# v1.net
KiCad netlist of a schematic drawn in EAGLE
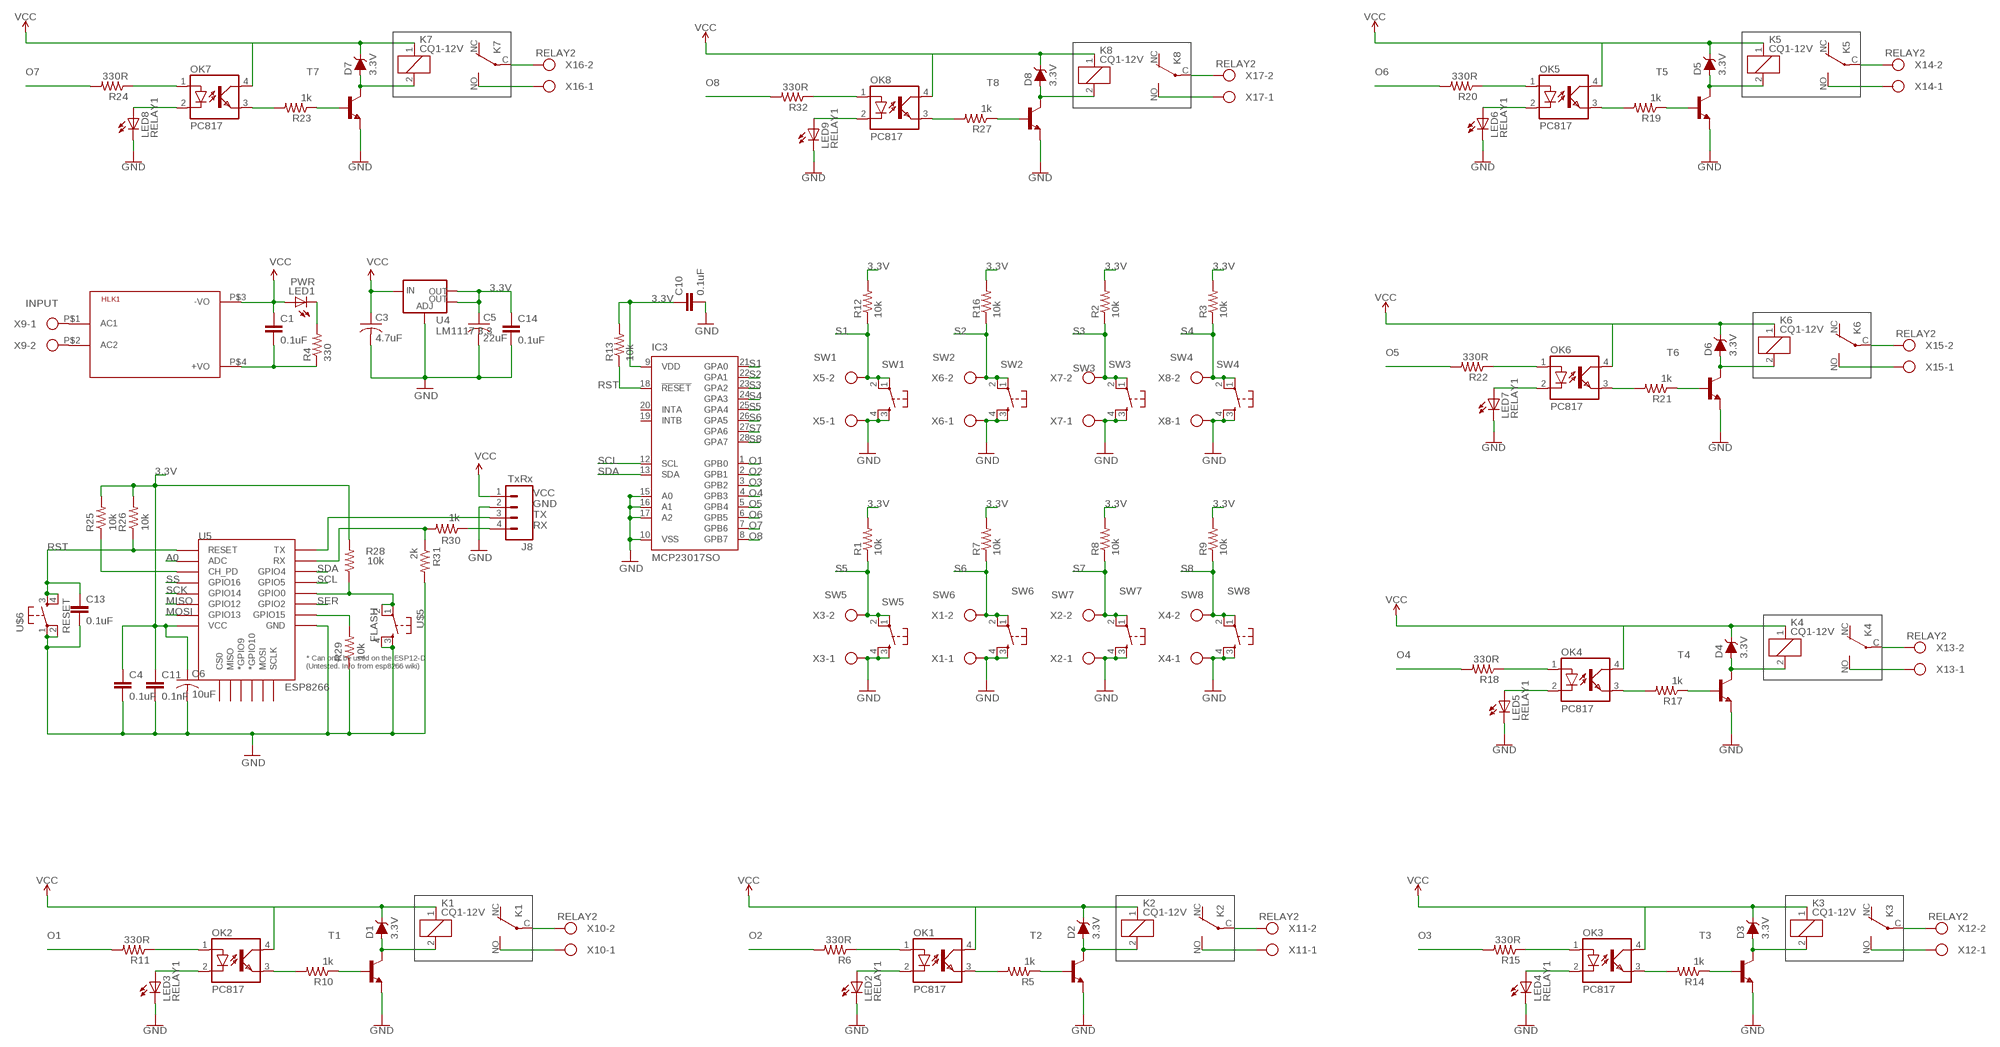
[diagram p0: schematic, sheet 1]

(export (version "E")
  (design (tool "Eeschema 10.0.6"))
  (components
    (comp (ref "C1")
      (value "0.1uF")
      (footprint "eagle-import:0805")
      (libsource (lib "eagle-import") (part "CAP0805"))
    )
    (comp (ref "C3")
      (value "4.7uF")
      (footprint "eagle-import:C1206")
      (libsource (lib "eagle-import") (part "C-USC1206"))
    )
    (comp (ref "C4")
      (value "0.1uF")
      (footprint "eagle-import:0805")
      (libsource (lib "eagle-import") (part "CAP0805"))
    )
    (comp (ref "C5")
      (value "22uF")
      (footprint "eagle-import:C1206")
      (libsource (lib "eagle-import") (part "C-USC1206"))
    )
    (comp (ref "C6")
      (value "10uF")
      (footprint "eagle-import:C1206")
      (libsource (lib "eagle-import") (part "C-USC1206"))
    )
    (comp (ref "C10")
      (value "0.1uF")
      (footprint "eagle-import:0805")
      (libsource (lib "eagle-import") (part "CAP0805"))
    )
    (comp (ref "C11")
      (value "0.1nF")
      (footprint "eagle-import:0805")
      (libsource (lib "eagle-import") (part "CAP0805"))
    )
    (comp (ref "C13")
      (value "0.1uF")
      (footprint "eagle-import:0805")
      (libsource (lib "eagle-import") (part "CAP0805"))
    )
    (comp (ref "C14")
      (value "0.1uF")
      (footprint "eagle-import:0805")
      (libsource (lib "eagle-import") (part "CAP0805"))
    )
    (comp (ref "D1")
      (value "3.3V")
      (footprint "eagle-import:SOD-323")
      (libsource (lib "eagle-import") (part "DIODE-ZENER-MM3Z3V3T1G"))
    )
    (comp (ref "D2")
      (value "3.3V")
      (footprint "eagle-import:SOD-323")
      (libsource (lib "eagle-import") (part "DIODE-ZENER-MM3Z3V3T1G"))
    )
    (comp (ref "D3")
      (value "3.3V")
      (footprint "eagle-import:SOD-323")
      (libsource (lib "eagle-import") (part "DIODE-ZENER-MM3Z3V3T1G"))
    )
    (comp (ref "D4")
      (value "3.3V")
      (footprint "eagle-import:SOD-323")
      (libsource (lib "eagle-import") (part "DIODE-ZENER-MM3Z3V3T1G"))
    )
    (comp (ref "D5")
      (value "3.3V")
      (footprint "eagle-import:SOD-323")
      (libsource (lib "eagle-import") (part "DIODE-ZENER-MM3Z3V3T1G"))
    )
    (comp (ref "D6")
      (value "3.3V")
      (footprint "eagle-import:SOD-323")
      (libsource (lib "eagle-import") (part "DIODE-ZENER-MM3Z3V3T1G"))
    )
    (comp (ref "D7")
      (value "3.3V")
      (footprint "eagle-import:SOD-323")
      (libsource (lib "eagle-import") (part "DIODE-ZENER-MM3Z3V3T1G"))
    )
    (comp (ref "D8")
      (value "3.3V")
      (footprint "eagle-import:SOD-323")
      (libsource (lib "eagle-import") (part "DIODE-ZENER-MM3Z3V3T1G"))
    )
    (comp (ref "HLK1")
      (value "HLK-PM013W")
      (footprint "eagle-import:HLK-PM01")
      (libsource (lib "eagle-import") (part "HLK-PM013W"))
    )
    (comp (ref "IC3")
      (value "MCP23017SO")
      (footprint "eagle-import:SO28W")
      (fields (field (name "MF") "MICROCHIP") (field (name "MPN") "MCP23017-E/SO"))
      (libsource (lib "eagle-import") (part "MCP23017SO"))
    )
    (comp (ref "J8")
      (value "TxRx")
      (footprint "eagle-import:MOLEX-1X4")
      (libsource (lib "eagle-import") (part "M04POLAR"))
    )
    (comp (ref "K1")
      (value "CQ1-12V")
      (footprint "eagle-import:CQ1")
      (libsource (lib "eagle-import") (part "CQ1-12V"))
    )
    (comp (ref "K2")
      (value "CQ1-12V")
      (footprint "eagle-import:CQ1")
      (libsource (lib "eagle-import") (part "CQ1-12V"))
    )
    (comp (ref "K3")
      (value "CQ1-12V")
      (footprint "eagle-import:CQ1")
      (libsource (lib "eagle-import") (part "CQ1-12V"))
    )
    (comp (ref "K4")
      (value "CQ1-12V")
      (footprint "eagle-import:CQ1")
      (libsource (lib "eagle-import") (part "CQ1-12V"))
    )
    (comp (ref "K5")
      (value "CQ1-12V")
      (footprint "eagle-import:CQ1")
      (libsource (lib "eagle-import") (part "CQ1-12V"))
    )
    (comp (ref "K6")
      (value "CQ1-12V")
      (footprint "eagle-import:CQ1")
      (libsource (lib "eagle-import") (part "CQ1-12V"))
    )
    (comp (ref "K7")
      (value "CQ1-12V")
      (footprint "eagle-import:CQ1")
      (libsource (lib "eagle-import") (part "CQ1-12V"))
    )
    (comp (ref "K8")
      (value "CQ1-12V")
      (footprint "eagle-import:CQ1")
      (libsource (lib "eagle-import") (part "CQ1-12V"))
    )
    (comp (ref "LED1")
      (value "PWR")
      (footprint "eagle-import:CHIP-LED0805")
      (libsource (lib "eagle-import") (part "LEDCHIP-LED0805"))
    )
    (comp (ref "LED2")
      (value "RELAY1")
      (footprint "eagle-import:CHIP-LED0805")
      (libsource (lib "eagle-import") (part "LEDCHIP-LED0805"))
    )
    (comp (ref "LED3")
      (value "RELAY1")
      (footprint "eagle-import:CHIP-LED0805")
      (libsource (lib "eagle-import") (part "LEDCHIP-LED0805"))
    )
    (comp (ref "LED4")
      (value "RELAY1")
      (footprint "eagle-import:CHIP-LED0805")
      (libsource (lib "eagle-import") (part "LEDCHIP-LED0805"))
    )
    (comp (ref "LED5")
      (value "RELAY1")
      (footprint "eagle-import:CHIP-LED0805")
      (libsource (lib "eagle-import") (part "LEDCHIP-LED0805"))
    )
    (comp (ref "LED6")
      (value "RELAY1")
      (footprint "eagle-import:CHIP-LED0805")
      (libsource (lib "eagle-import") (part "LEDCHIP-LED0805"))
    )
    (comp (ref "LED7")
      (value "RELAY1")
      (footprint "eagle-import:CHIP-LED0805")
      (libsource (lib "eagle-import") (part "LEDCHIP-LED0805"))
    )
    (comp (ref "LED8")
      (value "RELAY1")
      (footprint "eagle-import:CHIP-LED0805")
      (libsource (lib "eagle-import") (part "LEDCHIP-LED0805"))
    )
    (comp (ref "LED9")
      (value "RELAY1")
      (footprint "eagle-import:CHIP-LED0805")
      (libsource (lib "eagle-import") (part "LEDCHIP-LED0805"))
    )
    (comp (ref "OK1")
      (value "PC817")
      (footprint "eagle-import:DIL04")
      (fields (field (name "MPN") "PC817X4J000F"))
      (libsource (lib "eagle-import") (part "PC817"))
    )
    (comp (ref "OK2")
      (value "PC817")
      (footprint "eagle-import:DIL04")
      (fields (field (name "MPN") "PC817X4J000F"))
      (libsource (lib "eagle-import") (part "PC817"))
    )
    (comp (ref "OK3")
      (value "PC817")
      (footprint "eagle-import:DIL04")
      (fields (field (name "MPN") "PC817X4J000F"))
      (libsource (lib "eagle-import") (part "PC817"))
    )
    (comp (ref "OK4")
      (value "PC817")
      (footprint "eagle-import:DIL04")
      (fields (field (name "MPN") "PC817X4J000F"))
      (libsource (lib "eagle-import") (part "PC817"))
    )
    (comp (ref "OK5")
      (value "PC817")
      (footprint "eagle-import:DIL04")
      (fields (field (name "MPN") "PC817X4J000F"))
      (libsource (lib "eagle-import") (part "PC817"))
    )
    (comp (ref "OK6")
      (value "PC817")
      (footprint "eagle-import:DIL04")
      (fields (field (name "MPN") "PC817X4J000F"))
      (libsource (lib "eagle-import") (part "PC817"))
    )
    (comp (ref "OK7")
      (value "PC817")
      (footprint "eagle-import:DIL04")
      (fields (field (name "MPN") "PC817X4J000F"))
      (libsource (lib "eagle-import") (part "PC817"))
    )
    (comp (ref "OK8")
      (value "PC817")
      (footprint "eagle-import:DIL04")
      (fields (field (name "MPN") "PC817X4J000F"))
      (libsource (lib "eagle-import") (part "PC817"))
    )
    (comp (ref "R1")
      (value "10k")
      (footprint "eagle-import:0805")
      (libsource (lib "eagle-import") (part "RESISTOR0805-RES"))
    )
    (comp (ref "R2")
      (value "10k")
      (footprint "eagle-import:0805")
      (libsource (lib "eagle-import") (part "RESISTOR0805-RES"))
    )
    (comp (ref "R3")
      (value "10k")
      (footprint "eagle-import:0805")
      (libsource (lib "eagle-import") (part "RESISTOR0805-RES"))
    )
    (comp (ref "R4")
      (value "330")
      (footprint "eagle-import:0805")
      (libsource (lib "eagle-import") (part "RESISTOR0805-RES"))
    )
    (comp (ref "R5")
      (value "1k")
      (footprint "eagle-import:0805")
      (libsource (lib "eagle-import") (part "RESISTOR0805-RES"))
    )
    (comp (ref "R6")
      (value "330R")
      (footprint "eagle-import:0805")
      (libsource (lib "eagle-import") (part "RESISTOR0805-RES"))
    )
    (comp (ref "R7")
      (value "10k")
      (footprint "eagle-import:0805")
      (libsource (lib "eagle-import") (part "RESISTOR0805-RES"))
    )
    (comp (ref "R8")
      (value "10k")
      (footprint "eagle-import:0805")
      (libsource (lib "eagle-import") (part "RESISTOR0805-RES"))
    )
    (comp (ref "R9")
      (value "10k")
      (footprint "eagle-import:0805")
      (libsource (lib "eagle-import") (part "RESISTOR0805-RES"))
    )
    (comp (ref "R10")
      (value "1k")
      (footprint "eagle-import:0805")
      (libsource (lib "eagle-import") (part "RESISTOR0805-RES"))
    )
    (comp (ref "R11")
      (value "330R")
      (footprint "eagle-import:0805")
      (libsource (lib "eagle-import") (part "RESISTOR0805-RES"))
    )
    (comp (ref "R12")
      (value "10k")
      (footprint "eagle-import:0805")
      (libsource (lib "eagle-import") (part "RESISTOR0805-RES"))
    )
    (comp (ref "R13")
      (value "10k")
      (footprint "eagle-import:0805")
      (libsource (lib "eagle-import") (part "RESISTOR0805-RES"))
    )
    (comp (ref "R14")
      (value "1k")
      (footprint "eagle-import:0805")
      (libsource (lib "eagle-import") (part "RESISTOR0805-RES"))
    )
    (comp (ref "R15")
      (value "330R")
      (footprint "eagle-import:0805")
      (libsource (lib "eagle-import") (part "RESISTOR0805-RES"))
    )
    (comp (ref "R16")
      (value "10k")
      (footprint "eagle-import:0805")
      (libsource (lib "eagle-import") (part "RESISTOR0805-RES"))
    )
    (comp (ref "R17")
      (value "1k")
      (footprint "eagle-import:0805")
      (libsource (lib "eagle-import") (part "RESISTOR0805-RES"))
    )
    (comp (ref "R18")
      (value "330R")
      (footprint "eagle-import:0805")
      (libsource (lib "eagle-import") (part "RESISTOR0805-RES"))
    )
    (comp (ref "R19")
      (value "1k")
      (footprint "eagle-import:0805")
      (libsource (lib "eagle-import") (part "RESISTOR0805-RES"))
    )
    (comp (ref "R20")
      (value "330R")
      (footprint "eagle-import:0805")
      (libsource (lib "eagle-import") (part "RESISTOR0805-RES"))
    )
    (comp (ref "R21")
      (value "1k")
      (footprint "eagle-import:0805")
      (libsource (lib "eagle-import") (part "RESISTOR0805-RES"))
    )
    (comp (ref "R22")
      (value "330R")
      (footprint "eagle-import:0805")
      (libsource (lib "eagle-import") (part "RESISTOR0805-RES"))
    )
    (comp (ref "R23")
      (value "1k")
      (footprint "eagle-import:0805")
      (libsource (lib "eagle-import") (part "RESISTOR0805-RES"))
    )
    (comp (ref "R24")
      (value "330R")
      (footprint "eagle-import:0805")
      (libsource (lib "eagle-import") (part "RESISTOR0805-RES"))
    )
    (comp (ref "R25")
      (value "10k")
      (footprint "eagle-import:0805")
      (libsource (lib "eagle-import") (part "RESISTOR0805-RES"))
    )
    (comp (ref "R26")
      (value "10k")
      (footprint "eagle-import:0805")
      (libsource (lib "eagle-import") (part "RESISTOR0805-RES"))
    )
    (comp (ref "R27")
      (value "1k")
      (footprint "eagle-import:0805")
      (libsource (lib "eagle-import") (part "RESISTOR0805-RES"))
    )
    (comp (ref "R28")
      (value "10k")
      (footprint "eagle-import:0805")
      (libsource (lib "eagle-import") (part "RESISTOR0805-RES"))
    )
    (comp (ref "R29")
      (value "10k")
      (footprint "eagle-import:0805")
      (libsource (lib "eagle-import") (part "RESISTOR0805-RES"))
    )
    (comp (ref "R30")
      (value "1k")
      (footprint "eagle-import:0805")
      (libsource (lib "eagle-import") (part "RESISTOR0805-RES"))
    )
    (comp (ref "R31")
      (value "2k")
      (footprint "eagle-import:0805")
      (libsource (lib "eagle-import") (part "RESISTOR0805-RES"))
    )
    (comp (ref "R32")
      (value "330R")
      (footprint "eagle-import:0805")
      (libsource (lib "eagle-import") (part "RESISTOR0805-RES"))
    )
    (comp (ref "T1")
      (value "-NPN-SOT23-BEC")
      (footprint "eagle-import:SOT23-BEC")
      (libsource (lib "eagle-import") (part "-NPN-SOT23-BEC"))
    )
    (comp (ref "T2")
      (value "-NPN-SOT23-BEC")
      (footprint "eagle-import:SOT23-BEC")
      (libsource (lib "eagle-import") (part "-NPN-SOT23-BEC"))
    )
    (comp (ref "T3")
      (value "-NPN-SOT23-BEC")
      (footprint "eagle-import:SOT23-BEC")
      (libsource (lib "eagle-import") (part "-NPN-SOT23-BEC"))
    )
    (comp (ref "T4")
      (value "-NPN-SOT23-BEC")
      (footprint "eagle-import:SOT23-BEC")
      (libsource (lib "eagle-import") (part "-NPN-SOT23-BEC"))
    )
    (comp (ref "T5")
      (value "-NPN-SOT23-BEC")
      (footprint "eagle-import:SOT23-BEC")
      (libsource (lib "eagle-import") (part "-NPN-SOT23-BEC"))
    )
    (comp (ref "T6")
      (value "-NPN-SOT23-BEC")
      (footprint "eagle-import:SOT23-BEC")
      (libsource (lib "eagle-import") (part "-NPN-SOT23-BEC"))
    )
    (comp (ref "T7")
      (value "-NPN-SOT23-BEC")
      (footprint "eagle-import:SOT23-BEC")
      (libsource (lib "eagle-import") (part "-NPN-SOT23-BEC"))
    )
    (comp (ref "T8")
      (value "-NPN-SOT23-BEC")
      (footprint "eagle-import:SOT23-BEC")
      (libsource (lib "eagle-import") (part "-NPN-SOT23-BEC"))
    )
    (comp (ref "U$1")
      (value "SW1")
      (footprint "eagle-import:TAC-SWITCH-PTH")
      (libsource (lib "eagle-import") (part "TACTILE-SWITCH-PTH"))
    )
    (comp (ref "U$2")
      (value "SW2")
      (footprint "eagle-import:TAC-SWITCH-PTH")
      (libsource (lib "eagle-import") (part "TACTILE-SWITCH-PTH"))
    )
    (comp (ref "U$3")
      (value "SW5")
      (footprint "eagle-import:TAC-SWITCH-PTH")
      (libsource (lib "eagle-import") (part "TACTILE-SWITCH-PTH"))
    )
    (comp (ref "U$4")
      (value "SW3")
      (footprint "eagle-import:TAC-SWITCH-PTH")
      (libsource (lib "eagle-import") (part "TACTILE-SWITCH-PTH"))
    )
    (comp (ref "U$5")
      (value "FLASH")
      (footprint "eagle-import:TAC-SWITCH-PTH")
      (libsource (lib "eagle-import") (part "TACTILE-SWITCH-PTH"))
    )
    (comp (ref "U$6")
      (value "RESET")
      (footprint "eagle-import:TAC-SWITCH-PTH")
      (libsource (lib "eagle-import") (part "TACTILE-SWITCH-PTH"))
    )
    (comp (ref "U$7")
      (value "SW4")
      (footprint "eagle-import:TAC-SWITCH-PTH")
      (libsource (lib "eagle-import") (part "TACTILE-SWITCH-PTH"))
    )
    (comp (ref "U$8")
      (value "SW6")
      (footprint "eagle-import:TAC-SWITCH-PTH")
      (libsource (lib "eagle-import") (part "TACTILE-SWITCH-PTH"))
    )
    (comp (ref "U$9")
      (value "SW7")
      (footprint "eagle-import:TAC-SWITCH-PTH")
      (libsource (lib "eagle-import") (part "TACTILE-SWITCH-PTH"))
    )
    (comp (ref "U$10")
      (value "SW8")
      (footprint "eagle-import:TAC-SWITCH-PTH")
      (libsource (lib "eagle-import") (part "TACTILE-SWITCH-PTH"))
    )
    (comp (ref "U4")
      (value "LM1117 3.3")
      (footprint "eagle-import:SOT223")
      (libsource (lib "eagle-import") (part "V_REG_LM1117SOT223"))
    )
    (comp (ref "U5")
      (value "ESP8266")
      (footprint "eagle-import:ESP12E-SMD")
      (libsource (lib "eagle-import") (part "ESP12ESMD"))
    )
    (comp (ref "X1")
      (value "SW6")
      (footprint "eagle-import:W237-102")
      (fields (field (name "MPN") "237-102"))
      (libsource (lib "eagle-import") (part "W237-102"))
    )
    (comp (ref "X2")
      (value "SW7")
      (footprint "eagle-import:W237-102")
      (fields (field (name "MPN") "237-102"))
      (libsource (lib "eagle-import") (part "W237-102"))
    )
    (comp (ref "X3")
      (value "SW5")
      (footprint "eagle-import:W237-102")
      (fields (field (name "MPN") "237-102"))
      (libsource (lib "eagle-import") (part "W237-102"))
    )
    (comp (ref "X4")
      (value "SW8")
      (footprint "eagle-import:W237-102")
      (fields (field (name "MPN") "237-102"))
      (libsource (lib "eagle-import") (part "W237-102"))
    )
    (comp (ref "X5")
      (value "SW1")
      (footprint "eagle-import:W237-102")
      (fields (field (name "MPN") "237-102"))
      (libsource (lib "eagle-import") (part "W237-102"))
    )
    (comp (ref "X6")
      (value "SW2")
      (footprint "eagle-import:W237-102")
      (fields (field (name "MPN") "237-102"))
      (libsource (lib "eagle-import") (part "W237-102"))
    )
    (comp (ref "X7")
      (value "SW3")
      (footprint "eagle-import:W237-102")
      (fields (field (name "MPN") "237-102"))
      (libsource (lib "eagle-import") (part "W237-102"))
    )
    (comp (ref "X8")
      (value "SW4")
      (footprint "eagle-import:W237-102")
      (fields (field (name "MPN") "237-102"))
      (libsource (lib "eagle-import") (part "W237-102"))
    )
    (comp (ref "X9")
      (value "INPUT")
      (footprint "eagle-import:W237-102")
      (fields (field (name "MPN") "237-102"))
      (libsource (lib "eagle-import") (part "W237-102"))
    )
    (comp (ref "X10")
      (value "RELAY2")
      (footprint "eagle-import:W237-102")
      (fields (field (name "MPN") "237-102"))
      (libsource (lib "eagle-import") (part "W237-102"))
    )
    (comp (ref "X11")
      (value "RELAY2")
      (footprint "eagle-import:W237-102")
      (fields (field (name "MPN") "237-102"))
      (libsource (lib "eagle-import") (part "W237-102"))
    )
    (comp (ref "X12")
      (value "RELAY2")
      (footprint "eagle-import:W237-102")
      (fields (field (name "MPN") "237-102"))
      (libsource (lib "eagle-import") (part "W237-102"))
    )
    (comp (ref "X13")
      (value "RELAY2")
      (footprint "eagle-import:W237-102")
      (fields (field (name "MPN") "237-102"))
      (libsource (lib "eagle-import") (part "W237-102"))
    )
    (comp (ref "X14")
      (value "RELAY2")
      (footprint "eagle-import:W237-102")
      (fields (field (name "MPN") "237-102"))
      (libsource (lib "eagle-import") (part "W237-102"))
    )
    (comp (ref "X15")
      (value "RELAY2")
      (footprint "eagle-import:W237-102")
      (fields (field (name "MPN") "237-102"))
      (libsource (lib "eagle-import") (part "W237-102"))
    )
    (comp (ref "X16")
      (value "RELAY2")
      (footprint "eagle-import:W237-102")
      (fields (field (name "MPN") "237-102"))
      (libsource (lib "eagle-import") (part "W237-102"))
    )
    (comp (ref "X17")
      (value "RELAY2")
      (footprint "eagle-import:W237-102")
      (fields (field (name "MPN") "237-102"))
      (libsource (lib "eagle-import") (part "W237-102"))
    )
  )
  (nets
    (net (code "1") (name "/3.3V") (class "Default")
      (node (ref "C10") (pin "1") (pinfunction "1_1") (pintype "passive"))
      (node (ref "C11") (pin "1") (pinfunction "1_1") (pintype "passive"))
      (node (ref "C14") (pin "1") (pinfunction "1_1") (pintype "passive"))
      (node (ref "C4") (pin "1") (pinfunction "1_1") (pintype "passive"))
      (node (ref "C5") (pin "1") (pinfunction "1_1") (pintype "passive"))
      (node (ref "C6") (pin "1") (pinfunction "1_1") (pintype "passive"))
      (node (ref "IC3") (pin "9") (pinfunction "VDD_9") (pintype "power_in"))
      (node (ref "R1") (pin "2") (pinfunction "2_2") (pintype "passive"))
      (node (ref "R12") (pin "2") (pinfunction "2_2") (pintype "passive"))
      (node (ref "R13") (pin "2") (pinfunction "2_2") (pintype "passive"))
      (node (ref "R16") (pin "2") (pinfunction "2_2") (pintype "passive"))
      (node (ref "R2") (pin "2") (pinfunction "2_2") (pintype "passive"))
      (node (ref "R25") (pin "2") (pinfunction "2_2") (pintype "passive"))
      (node (ref "R26") (pin "2") (pinfunction "2_2") (pintype "passive"))
      (node (ref "R28") (pin "2") (pinfunction "2_2") (pintype "passive"))
      (node (ref "R3") (pin "2") (pinfunction "2_2") (pintype "passive"))
      (node (ref "R7") (pin "2") (pinfunction "2_2") (pintype "passive"))
      (node (ref "R8") (pin "2") (pinfunction "2_2") (pintype "passive"))
      (node (ref "R9") (pin "2") (pinfunction "2_2") (pintype "passive"))
      (node (ref "U4") (pin "2") (pinfunction "OUT_2") (pintype "output"))
      (node (ref "U4") (pin "4") (pinfunction "OUT_4") (pintype "output"))
      (node (ref "U5") (pin "VCC") (pinfunction "VCC_VCC") (pintype "bidirectional"))
    )
    (net (code "2") (name "/A0") (class "Default")
      (node (ref "U5") (pin "ADC") (pinfunction "ADC_ADC") (pintype "bidirectional"))
    )
    (net (code "3") (name "/MISO") (class "Default")
      (node (ref "U5") (pin "GPIO12") (pinfunction "GPIO12_GPIO12") (pintype "bidirectional"))
    )
    (net (code "4") (name "/MOSI") (class "Default")
      (node (ref "U5") (pin "GPIO13") (pinfunction "GPIO13_GPIO13") (pintype "bidirectional"))
    )
    (net (code "5") (name "/O1") (class "Default")
      (node (ref "IC3") (pin "1") (pinfunction "GPB0_1") (pintype "bidirectional"))
      (node (ref "R11") (pin "2") (pinfunction "2_2") (pintype "passive"))
    )
    (net (code "6") (name "/O2") (class "Default")
      (node (ref "IC3") (pin "2") (pinfunction "GPB1_2") (pintype "bidirectional"))
      (node (ref "R6") (pin "2") (pinfunction "2_2") (pintype "passive"))
    )
    (net (code "7") (name "/O3") (class "Default")
      (node (ref "IC3") (pin "3") (pinfunction "GPB2_3") (pintype "bidirectional"))
      (node (ref "R15") (pin "2") (pinfunction "2_2") (pintype "passive"))
    )
    (net (code "8") (name "/O4") (class "Default")
      (node (ref "IC3") (pin "4") (pinfunction "GPB3_4") (pintype "bidirectional"))
      (node (ref "R18") (pin "2") (pinfunction "2_2") (pintype "passive"))
    )
    (net (code "9") (name "/O5") (class "Default")
      (node (ref "IC3") (pin "5") (pinfunction "GPB4_5") (pintype "bidirectional"))
      (node (ref "R22") (pin "2") (pinfunction "2_2") (pintype "passive"))
    )
    (net (code "10") (name "/O6") (class "Default")
      (node (ref "IC3") (pin "6") (pinfunction "GPB5_6") (pintype "bidirectional"))
      (node (ref "R20") (pin "2") (pinfunction "2_2") (pintype "passive"))
    )
    (net (code "11") (name "/O7") (class "Default")
      (node (ref "IC3") (pin "7") (pinfunction "GPB6_7") (pintype "bidirectional"))
      (node (ref "R24") (pin "2") (pinfunction "2_2") (pintype "passive"))
    )
    (net (code "12") (name "/O8") (class "Default")
      (node (ref "IC3") (pin "8") (pinfunction "GPB7_8") (pintype "bidirectional"))
      (node (ref "R32") (pin "2") (pinfunction "2_2") (pintype "passive"))
    )
    (net (code "13") (name "/RST") (class "Default")
      (node (ref "C13") (pin "1") (pinfunction "1_1") (pintype "passive"))
      (node (ref "IC3") (pin "18") (pinfunction "~{RESET}_18") (pintype "input"))
      (node (ref "R13") (pin "1") (pinfunction "1_1") (pintype "passive"))
      (node (ref "R26") (pin "1") (pinfunction "1_1") (pintype "passive"))
      (node (ref "U$6") (pin "3") (pinfunction "3_3") (pintype "passive"))
      (node (ref "U$6") (pin "4") (pinfunction "4_4") (pintype "passive"))
      (node (ref "U5") (pin "RESET") (pinfunction "RESET_RESET") (pintype "bidirectional"))
    )
    (net (code "14") (name "/RX") (class "Default")
      (node (ref "J8") (pin "4") (pinfunction "4_4") (pintype "passive"))
      (node (ref "R30") (pin "1") (pinfunction "1_1") (pintype "passive"))
    )
    (net (code "15") (name "/S1") (class "Default")
      (node (ref "IC3") (pin "21") (pinfunction "GPA0_21") (pintype "bidirectional"))
      (node (ref "R12") (pin "1") (pinfunction "1_1") (pintype "passive"))
      (node (ref "U$1") (pin "1") (pinfunction "1_1") (pintype "passive"))
      (node (ref "U$1") (pin "2") (pinfunction "2_2") (pintype "passive"))
      (node (ref "X5") (pin "2") (pinfunction "KL_2") (pintype "passive"))
    )
    (net (code "16") (name "/S2") (class "Default")
      (node (ref "IC3") (pin "22") (pinfunction "GPA1_22") (pintype "bidirectional"))
      (node (ref "R16") (pin "1") (pinfunction "1_1") (pintype "passive"))
      (node (ref "U$2") (pin "1") (pinfunction "1_1") (pintype "passive"))
      (node (ref "U$2") (pin "2") (pinfunction "2_2") (pintype "passive"))
      (node (ref "X6") (pin "2") (pinfunction "KL_2") (pintype "passive"))
    )
    (net (code "17") (name "/S3") (class "Default")
      (node (ref "IC3") (pin "23") (pinfunction "GPA2_23") (pintype "bidirectional"))
      (node (ref "R2") (pin "1") (pinfunction "1_1") (pintype "passive"))
      (node (ref "U$4") (pin "1") (pinfunction "1_1") (pintype "passive"))
      (node (ref "U$4") (pin "2") (pinfunction "2_2") (pintype "passive"))
      (node (ref "X7") (pin "2") (pinfunction "KL_2") (pintype "passive"))
    )
    (net (code "18") (name "/S4") (class "Default")
      (node (ref "IC3") (pin "24") (pinfunction "GPA3_24") (pintype "bidirectional"))
      (node (ref "R3") (pin "1") (pinfunction "1_1") (pintype "passive"))
      (node (ref "U$7") (pin "1") (pinfunction "1_1") (pintype "passive"))
      (node (ref "U$7") (pin "2") (pinfunction "2_2") (pintype "passive"))
      (node (ref "X8") (pin "2") (pinfunction "KL_2") (pintype "passive"))
    )
    (net (code "19") (name "/S5") (class "Default")
      (node (ref "IC3") (pin "25") (pinfunction "GPA4_25") (pintype "bidirectional"))
      (node (ref "R1") (pin "1") (pinfunction "1_1") (pintype "passive"))
      (node (ref "U$3") (pin "1") (pinfunction "1_1") (pintype "passive"))
      (node (ref "U$3") (pin "2") (pinfunction "2_2") (pintype "passive"))
      (node (ref "X3") (pin "2") (pinfunction "KL_2") (pintype "passive"))
    )
    (net (code "20") (name "/S6") (class "Default")
      (node (ref "IC3") (pin "26") (pinfunction "GPA5_26") (pintype "bidirectional"))
      (node (ref "R7") (pin "1") (pinfunction "1_1") (pintype "passive"))
      (node (ref "U$8") (pin "1") (pinfunction "1_1") (pintype "passive"))
      (node (ref "U$8") (pin "2") (pinfunction "2_2") (pintype "passive"))
      (node (ref "X1") (pin "2") (pinfunction "KL_2") (pintype "passive"))
    )
    (net (code "21") (name "/S7") (class "Default")
      (node (ref "IC3") (pin "27") (pinfunction "GPA6_27") (pintype "bidirectional"))
      (node (ref "R8") (pin "1") (pinfunction "1_1") (pintype "passive"))
      (node (ref "U$9") (pin "1") (pinfunction "1_1") (pintype "passive"))
      (node (ref "U$9") (pin "2") (pinfunction "2_2") (pintype "passive"))
      (node (ref "X2") (pin "2") (pinfunction "KL_2") (pintype "passive"))
    )
    (net (code "22") (name "/S8") (class "Default")
      (node (ref "IC3") (pin "28") (pinfunction "GPA7_28") (pintype "bidirectional"))
      (node (ref "R9") (pin "1") (pinfunction "1_1") (pintype "passive"))
      (node (ref "U$10") (pin "1") (pinfunction "1_1") (pintype "passive"))
      (node (ref "U$10") (pin "2") (pinfunction "2_2") (pintype "passive"))
      (node (ref "X4") (pin "2") (pinfunction "KL_2") (pintype "passive"))
    )
    (net (code "23") (name "/SCK") (class "Default")
      (node (ref "U5") (pin "GPIO14") (pinfunction "GPIO14_GPIO14") (pintype "bidirectional"))
    )
    (net (code "24") (name "/SCL") (class "Default")
      (node (ref "IC3") (pin "12") (pinfunction "SCL_12") (pintype "input"))
      (node (ref "U5") (pin "GPIO5") (pinfunction "GPIO5_GPIO5") (pintype "bidirectional"))
    )
    (net (code "25") (name "/SDA") (class "Default")
      (node (ref "IC3") (pin "13") (pinfunction "SDA_13") (pintype "bidirectional"))
      (node (ref "U5") (pin "GPIO4") (pinfunction "GPIO4_GPIO4") (pintype "bidirectional"))
    )
    (net (code "26") (name "/SER") (class "Default")
      (node (ref "U5") (pin "GPIO2") (pinfunction "GPIO2_GPIO2") (pintype "bidirectional"))
    )
    (net (code "27") (name "/SS") (class "Default")
      (node (ref "U5") (pin "GPIO16") (pinfunction "GPIO16_GPIO16") (pintype "bidirectional"))
    )
    (net (code "28") (name "/TX") (class "Default")
      (node (ref "J8") (pin "3") (pinfunction "3_3") (pintype "passive"))
      (node (ref "U5") (pin "TXD0") (pinfunction "TX_TXD0") (pintype "bidirectional"))
    )
    (net (code "29") (name "GND") (class "Default")
      (node (ref "C10") (pin "2") (pinfunction "2_2") (pintype "passive"))
      (node (ref "C11") (pin "2") (pinfunction "2_2") (pintype "passive"))
      (node (ref "C13") (pin "2") (pinfunction "2_2") (pintype "passive"))
      (node (ref "C14") (pin "2") (pinfunction "2_2") (pintype "passive"))
      (node (ref "C3") (pin "2") (pinfunction "2_2") (pintype "passive"))
      (node (ref "C4") (pin "2") (pinfunction "2_2") (pintype "passive"))
      (node (ref "C5") (pin "2") (pinfunction "2_2") (pintype "passive"))
      (node (ref "C6") (pin "2") (pinfunction "2_2") (pintype "passive"))
      (node (ref "IC3") (pin "10") (pinfunction "VSS_10") (pintype "power_in"))
      (node (ref "IC3") (pin "15") (pinfunction "A0_15") (pintype "input"))
      (node (ref "IC3") (pin "16") (pinfunction "A1_16") (pintype "input"))
      (node (ref "IC3") (pin "17") (pinfunction "A2_17") (pintype "input"))
      (node (ref "J8") (pin "2") (pinfunction "2_2") (pintype "passive"))
      (node (ref "LED2") (pin "C") (pinfunction "C_C") (pintype "passive"))
      (node (ref "LED3") (pin "C") (pinfunction "C_C") (pintype "passive"))
      (node (ref "LED4") (pin "C") (pinfunction "C_C") (pintype "passive"))
      (node (ref "LED5") (pin "C") (pinfunction "C_C") (pintype "passive"))
      (node (ref "LED6") (pin "C") (pinfunction "C_C") (pintype "passive"))
      (node (ref "LED7") (pin "C") (pinfunction "C_C") (pintype "passive"))
      (node (ref "LED8") (pin "C") (pinfunction "C_C") (pintype "passive"))
      (node (ref "LED9") (pin "C") (pinfunction "C_C") (pintype "passive"))
      (node (ref "R29") (pin "1") (pinfunction "1_1") (pintype "passive"))
      (node (ref "R31") (pin "2") (pinfunction "2_2") (pintype "passive"))
      (node (ref "T1") (pin "E") (pinfunction "E_E") (pintype "passive"))
      (node (ref "T2") (pin "E") (pinfunction "E_E") (pintype "passive"))
      (node (ref "T3") (pin "E") (pinfunction "E_E") (pintype "passive"))
      (node (ref "T4") (pin "E") (pinfunction "E_E") (pintype "passive"))
      (node (ref "T5") (pin "E") (pinfunction "E_E") (pintype "passive"))
      (node (ref "T6") (pin "E") (pinfunction "E_E") (pintype "passive"))
      (node (ref "T7") (pin "E") (pinfunction "E_E") (pintype "passive"))
      (node (ref "T8") (pin "E") (pinfunction "E_E") (pintype "passive"))
      (node (ref "U$1") (pin "3") (pinfunction "3_3") (pintype "passive"))
      (node (ref "U$1") (pin "4") (pinfunction "4_4") (pintype "passive"))
      (node (ref "U$10") (pin "3") (pinfunction "3_3") (pintype "passive"))
      (node (ref "U$10") (pin "4") (pinfunction "4_4") (pintype "passive"))
      (node (ref "U$2") (pin "3") (pinfunction "3_3") (pintype "passive"))
      (node (ref "U$2") (pin "4") (pinfunction "4_4") (pintype "passive"))
      (node (ref "U$3") (pin "3") (pinfunction "3_3") (pintype "passive"))
      (node (ref "U$3") (pin "4") (pinfunction "4_4") (pintype "passive"))
      (node (ref "U$4") (pin "3") (pinfunction "3_3") (pintype "passive"))
      (node (ref "U$4") (pin "4") (pinfunction "4_4") (pintype "passive"))
      (node (ref "U$5") (pin "3") (pinfunction "3_3") (pintype "passive"))
      (node (ref "U$5") (pin "4") (pinfunction "4_4") (pintype "passive"))
      (node (ref "U$6") (pin "1") (pinfunction "1_1") (pintype "passive"))
      (node (ref "U$6") (pin "2") (pinfunction "2_2") (pintype "passive"))
      (node (ref "U$7") (pin "3") (pinfunction "3_3") (pintype "passive"))
      (node (ref "U$7") (pin "4") (pinfunction "4_4") (pintype "passive"))
      (node (ref "U$8") (pin "3") (pinfunction "3_3") (pintype "passive"))
      (node (ref "U$8") (pin "4") (pinfunction "4_4") (pintype "passive"))
      (node (ref "U$9") (pin "3") (pinfunction "3_3") (pintype "passive"))
      (node (ref "U$9") (pin "4") (pinfunction "4_4") (pintype "passive"))
      (node (ref "U4") (pin "1") (pinfunction "ADJ_1") (pintype "input"))
      (node (ref "U5") (pin "GND") (pinfunction "GND_GND") (pintype "bidirectional"))
      (node (ref "X1") (pin "1") (pinfunction "KL_1") (pintype "passive"))
      (node (ref "X2") (pin "1") (pinfunction "KL_1") (pintype "passive"))
      (node (ref "X3") (pin "1") (pinfunction "KL_1") (pintype "passive"))
      (node (ref "X4") (pin "1") (pinfunction "KL_1") (pintype "passive"))
      (node (ref "X5") (pin "1") (pinfunction "KL_1") (pintype "passive"))
      (node (ref "X6") (pin "1") (pinfunction "KL_1") (pintype "passive"))
      (node (ref "X7") (pin "1") (pinfunction "KL_1") (pintype "passive"))
      (node (ref "X8") (pin "1") (pinfunction "KL_1") (pintype "passive"))
    )
    (net (code "30") (name "Net-(D1-PadA)") (class "Default")
      (node (ref "D1") (pin "A") (pinfunction "A_A") (pintype "passive"))
      (node (ref "K1") (pin "2") (pinfunction "2_2") (pintype "passive"))
      (node (ref "T1") (pin "C") (pinfunction "C_C") (pintype "passive"))
    )
    (net (code "31") (name "Net-(D2-PadA)") (class "Default")
      (node (ref "D2") (pin "A") (pinfunction "A_A") (pintype "passive"))
      (node (ref "K2") (pin "2") (pinfunction "2_2") (pintype "passive"))
      (node (ref "T2") (pin "C") (pinfunction "C_C") (pintype "passive"))
    )
    (net (code "32") (name "Net-(D3-PadA)") (class "Default")
      (node (ref "D3") (pin "A") (pinfunction "A_A") (pintype "passive"))
      (node (ref "K3") (pin "2") (pinfunction "2_2") (pintype "passive"))
      (node (ref "T3") (pin "C") (pinfunction "C_C") (pintype "passive"))
    )
    (net (code "33") (name "Net-(D4-PadA)") (class "Default")
      (node (ref "D4") (pin "A") (pinfunction "A_A") (pintype "passive"))
      (node (ref "K4") (pin "2") (pinfunction "2_2") (pintype "passive"))
      (node (ref "T4") (pin "C") (pinfunction "C_C") (pintype "passive"))
    )
    (net (code "34") (name "Net-(D5-PadA)") (class "Default")
      (node (ref "D5") (pin "A") (pinfunction "A_A") (pintype "passive"))
      (node (ref "K5") (pin "2") (pinfunction "2_2") (pintype "passive"))
      (node (ref "T5") (pin "C") (pinfunction "C_C") (pintype "passive"))
    )
    (net (code "35") (name "Net-(D6-PadA)") (class "Default")
      (node (ref "D6") (pin "A") (pinfunction "A_A") (pintype "passive"))
      (node (ref "K6") (pin "2") (pinfunction "2_2") (pintype "passive"))
      (node (ref "T6") (pin "C") (pinfunction "C_C") (pintype "passive"))
    )
    (net (code "36") (name "Net-(D7-PadA)") (class "Default")
      (node (ref "D7") (pin "A") (pinfunction "A_A") (pintype "passive"))
      (node (ref "K7") (pin "2") (pinfunction "2_2") (pintype "passive"))
      (node (ref "T7") (pin "C") (pinfunction "C_C") (pintype "passive"))
    )
    (net (code "37") (name "Net-(D8-PadA)") (class "Default")
      (node (ref "D8") (pin "A") (pinfunction "A_A") (pintype "passive"))
      (node (ref "K8") (pin "2") (pinfunction "2_2") (pintype "passive"))
      (node (ref "T8") (pin "C") (pinfunction "C_C") (pintype "passive"))
    )
    (net (code "38") (name "Net-(HLK1-+VO)") (class "Default")
      (node (ref "C1") (pin "2") (pinfunction "2_2") (pintype "passive"))
      (node (ref "HLK1") (pin "P$4") (pinfunction "+VO_P$4") (pintype "bidirectional"))
      (node (ref "R4") (pin "1") (pinfunction "1_1") (pintype "passive"))
    )
    (net (code "39") (name "Net-(HLK1-AC1)") (class "Default")
      (node (ref "HLK1") (pin "P$1") (pinfunction "AC1_P$1") (pintype "bidirectional"))
      (node (ref "X9") (pin "1") (pinfunction "KL_1") (pintype "passive"))
    )
    (net (code "40") (name "Net-(HLK1-AC2)") (class "Default")
      (node (ref "HLK1") (pin "P$2") (pinfunction "AC2_P$2") (pintype "bidirectional"))
      (node (ref "X9") (pin "2") (pinfunction "KL_2") (pintype "passive"))
    )
    (net (code "41") (name "Net-(K1B-P)") (class "Default")
      (node (ref "K1") (pin "C") (pinfunction "P_C") (pintype "passive"))
      (node (ref "X10") (pin "2") (pinfunction "KL_2") (pintype "passive"))
    )
    (net (code "42") (name "Net-(K1B-S)") (class "Default")
      (node (ref "K1") (pin "NO") (pinfunction "S_NO") (pintype "passive"))
      (node (ref "X10") (pin "1") (pinfunction "KL_1") (pintype "passive"))
    )
    (net (code "43") (name "Net-(K2B-P)") (class "Default")
      (node (ref "K2") (pin "C") (pinfunction "P_C") (pintype "passive"))
      (node (ref "X11") (pin "2") (pinfunction "KL_2") (pintype "passive"))
    )
    (net (code "44") (name "Net-(K2B-S)") (class "Default")
      (node (ref "K2") (pin "NO") (pinfunction "S_NO") (pintype "passive"))
      (node (ref "X11") (pin "1") (pinfunction "KL_1") (pintype "passive"))
    )
    (net (code "45") (name "Net-(K3B-P)") (class "Default")
      (node (ref "K3") (pin "C") (pinfunction "P_C") (pintype "passive"))
      (node (ref "X12") (pin "2") (pinfunction "KL_2") (pintype "passive"))
    )
    (net (code "46") (name "Net-(K3B-S)") (class "Default")
      (node (ref "K3") (pin "NO") (pinfunction "S_NO") (pintype "passive"))
      (node (ref "X12") (pin "1") (pinfunction "KL_1") (pintype "passive"))
    )
    (net (code "47") (name "Net-(K4B-P)") (class "Default")
      (node (ref "K4") (pin "C") (pinfunction "P_C") (pintype "passive"))
      (node (ref "X13") (pin "2") (pinfunction "KL_2") (pintype "passive"))
    )
    (net (code "48") (name "Net-(K4B-S)") (class "Default")
      (node (ref "K4") (pin "NO") (pinfunction "S_NO") (pintype "passive"))
      (node (ref "X13") (pin "1") (pinfunction "KL_1") (pintype "passive"))
    )
    (net (code "49") (name "Net-(K5B-P)") (class "Default")
      (node (ref "K5") (pin "C") (pinfunction "P_C") (pintype "passive"))
      (node (ref "X14") (pin "2") (pinfunction "KL_2") (pintype "passive"))
    )
    (net (code "50") (name "Net-(K5B-S)") (class "Default")
      (node (ref "K5") (pin "NO") (pinfunction "S_NO") (pintype "passive"))
      (node (ref "X14") (pin "1") (pinfunction "KL_1") (pintype "passive"))
    )
    (net (code "51") (name "Net-(K6B-P)") (class "Default")
      (node (ref "K6") (pin "C") (pinfunction "P_C") (pintype "passive"))
      (node (ref "X15") (pin "2") (pinfunction "KL_2") (pintype "passive"))
    )
    (net (code "52") (name "Net-(K6B-S)") (class "Default")
      (node (ref "K6") (pin "NO") (pinfunction "S_NO") (pintype "passive"))
      (node (ref "X15") (pin "1") (pinfunction "KL_1") (pintype "passive"))
    )
    (net (code "53") (name "Net-(K7B-P)") (class "Default")
      (node (ref "K7") (pin "C") (pinfunction "P_C") (pintype "passive"))
      (node (ref "X16") (pin "2") (pinfunction "KL_2") (pintype "passive"))
    )
    (net (code "54") (name "Net-(K7B-S)") (class "Default")
      (node (ref "K7") (pin "NO") (pinfunction "S_NO") (pintype "passive"))
      (node (ref "X16") (pin "1") (pinfunction "KL_1") (pintype "passive"))
    )
    (net (code "55") (name "Net-(K8B-P)") (class "Default")
      (node (ref "K8") (pin "C") (pinfunction "P_C") (pintype "passive"))
      (node (ref "X17") (pin "2") (pinfunction "KL_2") (pintype "passive"))
    )
    (net (code "56") (name "Net-(K8B-S)") (class "Default")
      (node (ref "K8") (pin "NO") (pinfunction "S_NO") (pintype "passive"))
      (node (ref "X17") (pin "1") (pinfunction "KL_1") (pintype "passive"))
    )
    (net (code "57") (name "Net-(LED1-PadC)") (class "Default")
      (node (ref "LED1") (pin "C") (pinfunction "C_C") (pintype "passive"))
      (node (ref "R4") (pin "2") (pinfunction "2_2") (pintype "passive"))
    )
    (net (code "58") (name "Net-(OK1-A)") (class "Default")
      (node (ref "OK1") (pin "1") (pinfunction "A_1") (pintype "passive"))
      (node (ref "R6") (pin "1") (pinfunction "1_1") (pintype "passive"))
    )
    (net (code "59") (name "Net-(OK1-C)") (class "Default")
      (node (ref "LED2") (pin "A") (pinfunction "A_A") (pintype "passive"))
      (node (ref "OK1") (pin "2") (pinfunction "C_2") (pintype "passive"))
    )
    (net (code "60") (name "Net-(OK1-EMIT)") (class "Default")
      (node (ref "OK1") (pin "3") (pinfunction "EMIT_3") (pintype "passive"))
      (node (ref "R5") (pin "2") (pinfunction "2_2") (pintype "passive"))
    )
    (net (code "61") (name "Net-(OK2-A)") (class "Default")
      (node (ref "OK2") (pin "1") (pinfunction "A_1") (pintype "passive"))
      (node (ref "R11") (pin "1") (pinfunction "1_1") (pintype "passive"))
    )
    (net (code "62") (name "Net-(OK2-C)") (class "Default")
      (node (ref "LED3") (pin "A") (pinfunction "A_A") (pintype "passive"))
      (node (ref "OK2") (pin "2") (pinfunction "C_2") (pintype "passive"))
    )
    (net (code "63") (name "Net-(OK2-EMIT)") (class "Default")
      (node (ref "OK2") (pin "3") (pinfunction "EMIT_3") (pintype "passive"))
      (node (ref "R10") (pin "2") (pinfunction "2_2") (pintype "passive"))
    )
    (net (code "64") (name "Net-(OK3-A)") (class "Default")
      (node (ref "OK3") (pin "1") (pinfunction "A_1") (pintype "passive"))
      (node (ref "R15") (pin "1") (pinfunction "1_1") (pintype "passive"))
    )
    (net (code "65") (name "Net-(OK3-C)") (class "Default")
      (node (ref "LED4") (pin "A") (pinfunction "A_A") (pintype "passive"))
      (node (ref "OK3") (pin "2") (pinfunction "C_2") (pintype "passive"))
    )
    (net (code "66") (name "Net-(OK3-EMIT)") (class "Default")
      (node (ref "OK3") (pin "3") (pinfunction "EMIT_3") (pintype "passive"))
      (node (ref "R14") (pin "2") (pinfunction "2_2") (pintype "passive"))
    )
    (net (code "67") (name "Net-(OK4-A)") (class "Default")
      (node (ref "OK4") (pin "1") (pinfunction "A_1") (pintype "passive"))
      (node (ref "R18") (pin "1") (pinfunction "1_1") (pintype "passive"))
    )
    (net (code "68") (name "Net-(OK4-C)") (class "Default")
      (node (ref "LED5") (pin "A") (pinfunction "A_A") (pintype "passive"))
      (node (ref "OK4") (pin "2") (pinfunction "C_2") (pintype "passive"))
    )
    (net (code "69") (name "Net-(OK4-EMIT)") (class "Default")
      (node (ref "OK4") (pin "3") (pinfunction "EMIT_3") (pintype "passive"))
      (node (ref "R17") (pin "2") (pinfunction "2_2") (pintype "passive"))
    )
    (net (code "70") (name "Net-(OK5-A)") (class "Default")
      (node (ref "OK5") (pin "1") (pinfunction "A_1") (pintype "passive"))
      (node (ref "R20") (pin "1") (pinfunction "1_1") (pintype "passive"))
    )
    (net (code "71") (name "Net-(OK5-C)") (class "Default")
      (node (ref "LED6") (pin "A") (pinfunction "A_A") (pintype "passive"))
      (node (ref "OK5") (pin "2") (pinfunction "C_2") (pintype "passive"))
    )
    (net (code "72") (name "Net-(OK5-EMIT)") (class "Default")
      (node (ref "OK5") (pin "3") (pinfunction "EMIT_3") (pintype "passive"))
      (node (ref "R19") (pin "2") (pinfunction "2_2") (pintype "passive"))
    )
    (net (code "73") (name "Net-(OK6-A)") (class "Default")
      (node (ref "OK6") (pin "1") (pinfunction "A_1") (pintype "passive"))
      (node (ref "R22") (pin "1") (pinfunction "1_1") (pintype "passive"))
    )
    (net (code "74") (name "Net-(OK6-C)") (class "Default")
      (node (ref "LED7") (pin "A") (pinfunction "A_A") (pintype "passive"))
      (node (ref "OK6") (pin "2") (pinfunction "C_2") (pintype "passive"))
    )
    (net (code "75") (name "Net-(OK6-EMIT)") (class "Default")
      (node (ref "OK6") (pin "3") (pinfunction "EMIT_3") (pintype "passive"))
      (node (ref "R21") (pin "2") (pinfunction "2_2") (pintype "passive"))
    )
    (net (code "76") (name "Net-(OK7-A)") (class "Default")
      (node (ref "OK7") (pin "1") (pinfunction "A_1") (pintype "passive"))
      (node (ref "R24") (pin "1") (pinfunction "1_1") (pintype "passive"))
    )
    (net (code "77") (name "Net-(OK7-C)") (class "Default")
      (node (ref "LED8") (pin "A") (pinfunction "A_A") (pintype "passive"))
      (node (ref "OK7") (pin "2") (pinfunction "C_2") (pintype "passive"))
    )
    (net (code "78") (name "Net-(OK7-EMIT)") (class "Default")
      (node (ref "OK7") (pin "3") (pinfunction "EMIT_3") (pintype "passive"))
      (node (ref "R23") (pin "2") (pinfunction "2_2") (pintype "passive"))
    )
    (net (code "79") (name "Net-(OK8-A)") (class "Default")
      (node (ref "OK8") (pin "1") (pinfunction "A_1") (pintype "passive"))
      (node (ref "R32") (pin "1") (pinfunction "1_1") (pintype "passive"))
    )
    (net (code "80") (name "Net-(OK8-C)") (class "Default")
      (node (ref "LED9") (pin "A") (pinfunction "A_A") (pintype "passive"))
      (node (ref "OK8") (pin "2") (pinfunction "C_2") (pintype "passive"))
    )
    (net (code "81") (name "Net-(OK8-EMIT)") (class "Default")
      (node (ref "OK8") (pin "3") (pinfunction "EMIT_3") (pintype "passive"))
      (node (ref "R27") (pin "2") (pinfunction "2_2") (pintype "passive"))
    )
    (net (code "82") (name "Net-(R5-Pad1)") (class "Default")
      (node (ref "R5") (pin "1") (pinfunction "1_1") (pintype "passive"))
      (node (ref "T2") (pin "B") (pinfunction "B_B") (pintype "passive"))
    )
    (net (code "83") (name "Net-(R10-Pad1)") (class "Default")
      (node (ref "R10") (pin "1") (pinfunction "1_1") (pintype "passive"))
      (node (ref "T1") (pin "B") (pinfunction "B_B") (pintype "passive"))
    )
    (net (code "84") (name "Net-(R14-Pad1)") (class "Default")
      (node (ref "R14") (pin "1") (pinfunction "1_1") (pintype "passive"))
      (node (ref "T3") (pin "B") (pinfunction "B_B") (pintype "passive"))
    )
    (net (code "85") (name "Net-(R17-Pad1)") (class "Default")
      (node (ref "R17") (pin "1") (pinfunction "1_1") (pintype "passive"))
      (node (ref "T4") (pin "B") (pinfunction "B_B") (pintype "passive"))
    )
    (net (code "86") (name "Net-(R19-Pad1)") (class "Default")
      (node (ref "R19") (pin "1") (pinfunction "1_1") (pintype "passive"))
      (node (ref "T5") (pin "B") (pinfunction "B_B") (pintype "passive"))
    )
    (net (code "87") (name "Net-(R21-Pad1)") (class "Default")
      (node (ref "R21") (pin "1") (pinfunction "1_1") (pintype "passive"))
      (node (ref "T6") (pin "B") (pinfunction "B_B") (pintype "passive"))
    )
    (net (code "88") (name "Net-(R23-Pad1)") (class "Default")
      (node (ref "R23") (pin "1") (pinfunction "1_1") (pintype "passive"))
      (node (ref "T7") (pin "B") (pinfunction "B_B") (pintype "passive"))
    )
    (net (code "89") (name "Net-(R25-Pad1)") (class "Default")
      (node (ref "R25") (pin "1") (pinfunction "1_1") (pintype "passive"))
      (node (ref "U5") (pin "CH_PD") (pinfunction "CH_PD_CH_PD") (pintype "bidirectional"))
    )
    (net (code "90") (name "Net-(R27-Pad1)") (class "Default")
      (node (ref "R27") (pin "1") (pinfunction "1_1") (pintype "passive"))
      (node (ref "T8") (pin "B") (pinfunction "B_B") (pintype "passive"))
    )
    (net (code "91") (name "Net-(R28-Pad1)") (class "Default")
      (node (ref "R28") (pin "1") (pinfunction "1_1") (pintype "passive"))
      (node (ref "U$5") (pin "1") (pinfunction "1_1") (pintype "passive"))
      (node (ref "U$5") (pin "2") (pinfunction "2_2") (pintype "passive"))
      (node (ref "U5") (pin "GPIO0") (pinfunction "GPIO0_GPIO0") (pintype "bidirectional"))
    )
    (net (code "92") (name "Net-(R29-Pad2)") (class "Default")
      (node (ref "R29") (pin "2") (pinfunction "2_2") (pintype "passive"))
      (node (ref "U5") (pin "GPIO15") (pinfunction "GPIO15_GPIO15") (pintype "bidirectional"))
    )
    (net (code "93") (name "Net-(U5-RX)") (class "Default")
      (node (ref "R30") (pin "2") (pinfunction "2_2") (pintype "passive"))
      (node (ref "R31") (pin "1") (pinfunction "1_1") (pintype "passive"))
      (node (ref "U5") (pin "RXD0") (pinfunction "RX_RXD0") (pintype "bidirectional"))
    )
    (net (code "94") (name "VCC") (class "Default")
      (node (ref "C1") (pin "1") (pinfunction "1_1") (pintype "passive"))
      (node (ref "C3") (pin "1") (pinfunction "1_1") (pintype "passive"))
      (node (ref "D1") (pin "C") (pinfunction "C_C") (pintype "passive"))
      (node (ref "D2") (pin "C") (pinfunction "C_C") (pintype "passive"))
      (node (ref "D3") (pin "C") (pinfunction "C_C") (pintype "passive"))
      (node (ref "D4") (pin "C") (pinfunction "C_C") (pintype "passive"))
      (node (ref "D5") (pin "C") (pinfunction "C_C") (pintype "passive"))
      (node (ref "D6") (pin "C") (pinfunction "C_C") (pintype "passive"))
      (node (ref "D7") (pin "C") (pinfunction "C_C") (pintype "passive"))
      (node (ref "D8") (pin "C") (pinfunction "C_C") (pintype "passive"))
      (node (ref "HLK1") (pin "P$3") (pinfunction "-VO_P$3") (pintype "bidirectional"))
      (node (ref "J8") (pin "1") (pinfunction "1_1") (pintype "passive"))
      (node (ref "K1") (pin "1") (pinfunction "1_1") (pintype "passive"))
      (node (ref "K2") (pin "1") (pinfunction "1_1") (pintype "passive"))
      (node (ref "K3") (pin "1") (pinfunction "1_1") (pintype "passive"))
      (node (ref "K4") (pin "1") (pinfunction "1_1") (pintype "passive"))
      (node (ref "K5") (pin "1") (pinfunction "1_1") (pintype "passive"))
      (node (ref "K6") (pin "1") (pinfunction "1_1") (pintype "passive"))
      (node (ref "K7") (pin "1") (pinfunction "1_1") (pintype "passive"))
      (node (ref "K8") (pin "1") (pinfunction "1_1") (pintype "passive"))
      (node (ref "LED1") (pin "A") (pinfunction "A_A") (pintype "passive"))
      (node (ref "OK1") (pin "4") (pinfunction "COL_4") (pintype "passive"))
      (node (ref "OK2") (pin "4") (pinfunction "COL_4") (pintype "passive"))
      (node (ref "OK3") (pin "4") (pinfunction "COL_4") (pintype "passive"))
      (node (ref "OK4") (pin "4") (pinfunction "COL_4") (pintype "passive"))
      (node (ref "OK5") (pin "4") (pinfunction "COL_4") (pintype "passive"))
      (node (ref "OK6") (pin "4") (pinfunction "COL_4") (pintype "passive"))
      (node (ref "OK7") (pin "4") (pinfunction "COL_4") (pintype "passive"))
      (node (ref "OK8") (pin "4") (pinfunction "COL_4") (pintype "passive"))
      (node (ref "U4") (pin "3") (pinfunction "IN_3") (pintype "input"))
    )
    (net (code "95") (name "unconnected-(IC3-INTA-Pad20)") (class "Default")
      (node (ref "IC3") (pin "20") (pinfunction "INTA_20") (pintype "output"))
    )
    (net (code "96") (name "unconnected-(IC3-INTB-Pad19)") (class "Default")
      (node (ref "IC3") (pin "19") (pinfunction "INTB_19") (pintype "output"))
    )
    (net (code "97") (name "unconnected-(K1B-O-PadNC)") (class "Default")
      (node (ref "K1") (pin "NC") (pinfunction "O_NC") (pintype "passive"))
    )
    (net (code "98") (name "unconnected-(K2B-O-PadNC)") (class "Default")
      (node (ref "K2") (pin "NC") (pinfunction "O_NC") (pintype "passive"))
    )
    (net (code "99") (name "unconnected-(K3B-O-PadNC)") (class "Default")
      (node (ref "K3") (pin "NC") (pinfunction "O_NC") (pintype "passive"))
    )
    (net (code "100") (name "unconnected-(K4B-O-PadNC)") (class "Default")
      (node (ref "K4") (pin "NC") (pinfunction "O_NC") (pintype "passive"))
    )
    (net (code "101") (name "unconnected-(K5B-O-PadNC)") (class "Default")
      (node (ref "K5") (pin "NC") (pinfunction "O_NC") (pintype "passive"))
    )
    (net (code "102") (name "unconnected-(K6B-O-PadNC)") (class "Default")
      (node (ref "K6") (pin "NC") (pinfunction "O_NC") (pintype "passive"))
    )
    (net (code "103") (name "unconnected-(K7B-O-PadNC)") (class "Default")
      (node (ref "K7") (pin "NC") (pinfunction "O_NC") (pintype "passive"))
    )
    (net (code "104") (name "unconnected-(K8B-O-PadNC)") (class "Default")
      (node (ref "K8") (pin "NC") (pinfunction "O_NC") (pintype "passive"))
    )
    (net (code "105") (name "unconnected-(U5-*GPIO9-PadGPIO9)") (class "Default")
      (node (ref "U5") (pin "GPIO9") (pinfunction "*GPIO9_GPIO9") (pintype "bidirectional"))
    )
    (net (code "106") (name "unconnected-(U5-*GPIO10-PadGPIO10)") (class "Default")
      (node (ref "U5") (pin "GPIO10") (pinfunction "*GPIO10_GPIO10") (pintype "bidirectional"))
    )
    (net (code "107") (name "unconnected-(U5-PadCS0)") (class "Default")
      (node (ref "U5") (pin "CS0") (pinfunction "CS0_CS0") (pintype "bidirectional"))
    )
    (net (code "108") (name "unconnected-(U5-PadMISO)") (class "Default")
      (node (ref "U5") (pin "MISO") (pinfunction "MISO_MISO") (pintype "bidirectional"))
    )
    (net (code "109") (name "unconnected-(U5-PadMOSI)") (class "Default")
      (node (ref "U5") (pin "MOSI") (pinfunction "MOSI_MOSI") (pintype "bidirectional"))
    )
    (net (code "110") (name "unconnected-(U5-PadSCLK)") (class "Default")
      (node (ref "U5") (pin "SCLK") (pinfunction "SCLK_SCLK") (pintype "bidirectional"))
    )
  )
)
